# BatteryCharger.net
KiCad netlist of a schematic drawn in Altium Designer
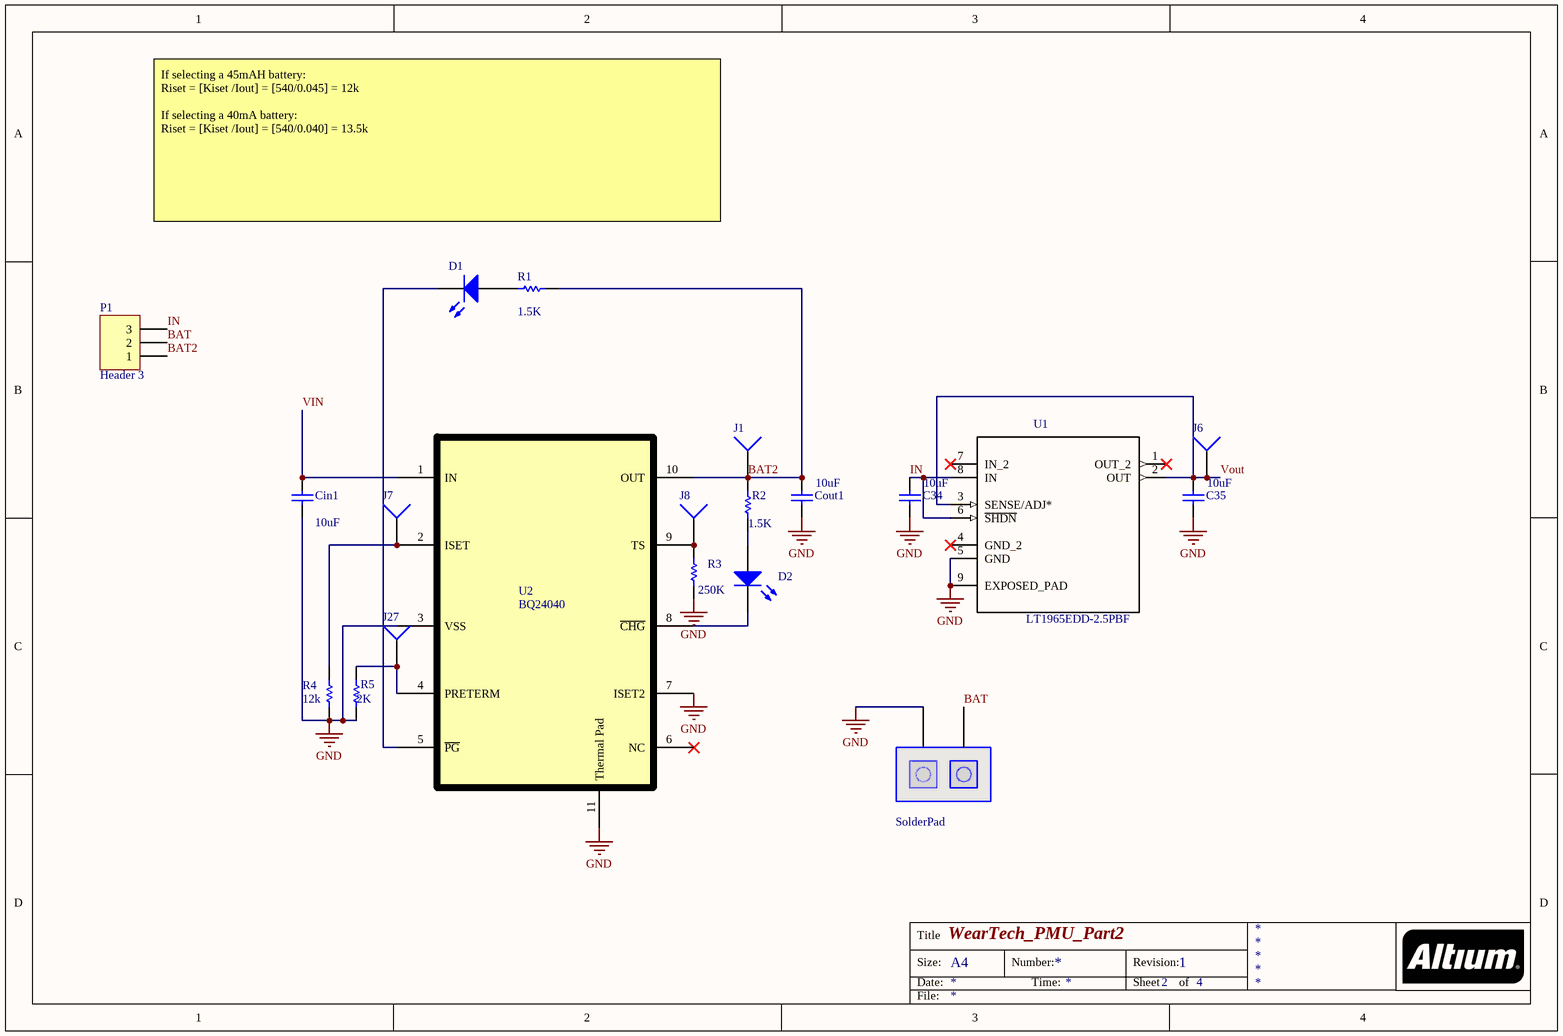
[diagram p0: BatteryCharger.SchDoc]

(export (version "E")
  (design (tool "Eeschema 10.0.6"))
  (components
    (comp (ref "1")
      (value "SolderPad")
      (footprint "bATTERY_CONNECTION")
      (description "Description")
      (fields
        (field (name "MANUFACTURE PART NUM") "Manufacture Part Num")
        (field (name "DIGIKEY PART NUMBER") "D")
      )
      (libsource (lib "WearTechSchLib") (part "SolderPad"))
    )
    (comp (ref "C34")
      (value "10uF")
      (footprint "1608[0603]")
      (description "CAP CER 10UF 4V X5R 0603")
      (fields (field (name "MANUFACTURE PART NUM") "06034D106MAT2A"))
      (libsource (lib "Miscellaneous Devices") (part "Cap"))
    )
    (comp (ref "C35")
      (value "10uF")
      (footprint "1608[0603]")
      (description "CAP CER 10UF 4V X5R 0603")
      (fields (field (name "MANUFACTURE PART NUM") "06034D106MAT2A"))
      (libsource (lib "Miscellaneous Devices") (part "Cap"))
    )
    (comp (ref "Cin1")
      (value "10uF")
      (footprint "1608[0603]")
      (description "CAP CER 10UF 6.3V X5R 0603")
      (fields (field (name "MANUFACTURE PART NUM") "GRM188R60J106ME47D"))
      (libsource (lib "Miscellaneous Devices") (part "Cap"))
    )
    (comp (ref "Cout1")
      (value "10uF")
      (footprint "1608[0603]")
      (description "CAP CER 10UF 4V X5R 0603")
      (fields (field (name "MANUFACTURE PART NUM") "06034D106MAT2A"))
      (libsource (lib "Miscellaneous Devices") (part "Cap"))
    )
    (comp (ref "D1")
      (value "LED0")
      (footprint "1608[0603]")
      (description "LED ORANGE DIFFUSED 0603 SMD")
      (fields (field (name "MANUFACTURE PART NUM") "LO L29K-H2K1-24-Z"))
      (libsource (lib "Miscellaneous Devices") (part "LED0"))
    )
    (comp (ref "D2")
      (value "LED0")
      (footprint "1608[0603]")
      (description "LED ORANGE DIFFUSED 0603 SMD")
      (fields (field (name "MANUFACTURE PART NUM") "LO L29K-H2K1-24-Z"))
      (libsource (lib "Miscellaneous Devices") (part "LED0"))
    )
    (comp (ref "J1")
      (value "Socket")
      (footprint "PIN1")
      (description "Description")
      (fields
        (field (name "MANUFACTURE PART NUM") "68000-200HLF")
        (field (name "DIGIKEY PART NUMBER") "609-5099-1-ND")
      )
      (libsource (lib "Miscellaneous Connectors") (part "Socket"))
    )
    (comp (ref "J6")
      (value "Socket")
      (footprint "PIN1")
      (description "Description")
      (fields
        (field (name "MANUFACTURE PART NUM") "68000-200HLF")
        (field (name "DIGIKEY PART NUMBER") "609-5099-1-ND")
      )
      (libsource (lib "Miscellaneous Connectors") (part "Socket"))
    )
    (comp (ref "J7")
      (value "Socket")
      (footprint "PIN1")
      (description "Description")
      (fields
        (field (name "MANUFACTURE PART NUM") "68000-200HLF")
        (field (name "DIGIKEY PART NUMBER") "609-5099-1-ND")
      )
      (libsource (lib "Miscellaneous Connectors") (part "Socket"))
    )
    (comp (ref "J8")
      (value "Socket")
      (footprint "PIN1")
      (description "Description")
      (fields
        (field (name "MANUFACTURE PART NUM") "68000-200HLF")
        (field (name "DIGIKEY PART NUMBER") "609-5099-1-ND")
      )
      (libsource (lib "Miscellaneous Connectors") (part "Socket"))
    )
    (comp (ref "J27")
      (value "Socket")
      (footprint "PIN1")
      (description "Description")
      (fields
        (field (name "MANUFACTURE PART NUM") "68000-200HLF")
        (field (name "DIGIKEY PART NUMBER") "609-5099-1-ND")
      )
      (libsource (lib "Miscellaneous Connectors") (part "Socket"))
    )
    (comp (ref "P1")
      (value "Header 3")
      (footprint "HDR1X3")
      (description "CONN HEADER 3 POS 2.54")
      (fields (field (name "MANUFACTURE PART NUM") "Manufacture Part Num"))
      (libsource (lib "Miscellaneous Connectors") (part "Header 3"))
    )
    (comp (ref "R1")
      (value "1.5K")
      (footprint "1608[0603]")
      (description "RES SMD 1.5K OHM 5% 1/10W 0603")
      (fields (field (name "MANUFACTURE PART NUM") "RC0603JR-071K5L"))
      (libsource (lib "Miscellaneous Devices") (part "Res1"))
    )
    (comp (ref "R2")
      (value "1.5K")
      (footprint "1608[0603]")
      (description "RES SMD 1.5K OHM 5% 1/10W 0603")
      (fields (field (name "MANUFACTURE PART NUM") "RC0603JR-071K5L"))
      (libsource (lib "Miscellaneous Devices") (part "Res1"))
    )
    (comp (ref "R3")
      (value "250K")
      (footprint "1608[0603]")
      (description "RES SMD 10K OHM 5% 1/16W 0402")
      (fields (field (name "MANUFACTURE PART NUM") "RC0402JR-0710KL"))
      (libsource (lib "Miscellaneous Devices") (part "Res1"))
    )
    (comp (ref "R4")
      (value "12k")
      (footprint "1608[0603]")
      (description "RES SMD 12K OHM 5% 1/10W 0603")
      (fields (field (name "MANUFACTURE PART NUM") "RC0603JR-0712KL"))
      (libsource (lib "Miscellaneous Devices") (part "Res1"))
    )
    (comp (ref "R5")
      (value "2K")
      (footprint "1608[0603]")
      (description "RES SMD 2K OHM 1% 1/10W 0603")
      (fields (field (name "MANUFACTURE PART NUM") "ERJ-3EKF2001V"))
      (libsource (lib "Miscellaneous Devices") (part "Res1"))
    )
    (comp (ref "U1")
      (value "LT1965EDD-2.5PBF")
      (footprint "LT1965")
      (description "IC REG LINEAR 2.5V 1.1A 8DFN")
      (fields (field (name "MANUFACTURE PART NUM") "LT1965IDD-2.5#PBF"))
      (libsource (lib "WearTechSchLib") (part "LT1965EDD-2.5PBF"))
    )
    (comp (ref "U2")
      (value "BQ24040")
      (footprint "BQ24040")
      (description "IC BATT CHG LI-ION 1 CELL 10SON")
      (fields
        (field (name "MANUFACTURE PART NUM") "BQ24040DSQT")
        (field (name "DIGIKEY PART NUMBER") "296-25136-1-ND")
      )
      (libsource (lib "WearTechSchLib") (part "BQ24040"))
    )
  )
  (nets
    (net (code "1") (name "/BAT") (class "Default")
      (node (ref "1") (pin "1") (pinfunction "BAT_1") (pintype "passive"))
      (node (ref "P1") (pin "2") (pinfunction "2_2") (pintype "passive"))
    )
    (net (code "2") (name "/BAT2") (class "Default")
      (node (ref "Cout1") (pin "1") (pinfunction "1_1") (pintype "passive"))
      (node (ref "J1") (pin "1") (pinfunction "1_1") (pintype "passive"))
      (node (ref "P1") (pin "1") (pinfunction "1_1") (pintype "passive"))
      (node (ref "R1") (pin "2") (pinfunction "2_2") (pintype "passive"))
      (node (ref "R2") (pin "1") (pinfunction "1_1") (pintype "passive"))
      (node (ref "U2") (pin "10") (pinfunction "OUT_10") (pintype "passive"))
    )
    (net (code "3") (name "/IN") (class "Default")
      (node (ref "C34") (pin "1") (pinfunction "1_1") (pintype "passive"))
      (node (ref "P1") (pin "3") (pinfunction "3_3") (pintype "passive"))
      (node (ref "U1") (pin "6") (pinfunction "~{SHDN}_6") (pintype "input"))
      (node (ref "U1") (pin "8") (pinfunction "IN_8") (pintype "power_in"))
    )
    (net (code "4") (name "/VIN") (class "Default")
      (node (ref "Cin1") (pin "1") (pinfunction "1_1") (pintype "passive"))
      (node (ref "U2") (pin "1") (pinfunction "IN_1") (pintype "passive"))
    )
    (net (code "5") (name "/Vout") (class "Default")
      (node (ref "C35") (pin "1") (pinfunction "1_1") (pintype "passive"))
      (node (ref "J6") (pin "1") (pinfunction "1_1") (pintype "passive"))
      (node (ref "U1") (pin "2") (pinfunction "OUT_2") (pintype "output"))
      (node (ref "U1") (pin "3") (pinfunction "SENSE/ADJ*_3") (pintype "input"))
    )
    (net (code "6") (name "GND") (class "Default")
      (node (ref "1") (pin "2") (pinfunction "GND_2") (pintype "passive"))
      (node (ref "C34") (pin "2") (pinfunction "2_2") (pintype "passive"))
      (node (ref "C35") (pin "2") (pinfunction "2_2") (pintype "passive"))
      (node (ref "Cin1") (pin "2") (pinfunction "2_2") (pintype "passive"))
      (node (ref "Cout1") (pin "2") (pinfunction "2_2") (pintype "passive"))
      (node (ref "R3") (pin "1") (pinfunction "1_1") (pintype "passive"))
      (node (ref "R4") (pin "2") (pinfunction "2_2") (pintype "passive"))
      (node (ref "R5") (pin "2") (pinfunction "2_2") (pintype "passive"))
      (node (ref "U1") (pin "5") (pinfunction "GND_5") (pintype "passive"))
      (node (ref "U1") (pin "9") (pinfunction "EXPOSED_PAD_9") (pintype "passive"))
      (node (ref "U2") (pin "11") (pinfunction "Thermal_Pad_11") (pintype "passive"))
      (node (ref "U2") (pin "3") (pinfunction "VSS_3") (pintype "passive"))
      (node (ref "U2") (pin "7") (pinfunction "ISET2_7") (pintype "passive"))
    )
    (net (code "7") (name "Net-(D1-A)") (class "Default")
      (node (ref "D1") (pin "1") (pinfunction "A_1") (pintype "passive"))
      (node (ref "R1") (pin "1") (pinfunction "1_1") (pintype "passive"))
    )
    (net (code "8") (name "Net-(D1-K)") (class "Default")
      (node (ref "D1") (pin "2") (pinfunction "K_2") (pintype "passive"))
      (node (ref "U2") (pin "5") (pinfunction "~{PG}_5") (pintype "passive"))
    )
    (net (code "9") (name "Net-(D2-A)") (class "Default")
      (node (ref "D2") (pin "1") (pinfunction "A_1") (pintype "passive"))
      (node (ref "R2") (pin "2") (pinfunction "2_2") (pintype "passive"))
    )
    (net (code "10") (name "Net-(D2-K)") (class "Default")
      (node (ref "D2") (pin "2") (pinfunction "K_2") (pintype "passive"))
      (node (ref "U2") (pin "8") (pinfunction "~{CHG}_8") (pintype "passive"))
    )
    (net (code "11") (name "Net-(U2-ISET)") (class "Default")
      (node (ref "J7") (pin "1") (pinfunction "1_1") (pintype "passive"))
      (node (ref "R4") (pin "1") (pinfunction "1_1") (pintype "passive"))
      (node (ref "U2") (pin "2") (pinfunction "ISET_2") (pintype "passive"))
    )
    (net (code "12") (name "Net-(U2-PRETERM)") (class "Default")
      (node (ref "J27") (pin "1") (pinfunction "1_1") (pintype "passive"))
      (node (ref "R5") (pin "1") (pinfunction "1_1") (pintype "passive"))
      (node (ref "U2") (pin "4") (pinfunction "PRETERM_4") (pintype "passive"))
    )
    (net (code "13") (name "Net-(U2-TS)") (class "Default")
      (node (ref "J8") (pin "1") (pinfunction "1_1") (pintype "passive"))
      (node (ref "R3") (pin "2") (pinfunction "2_2") (pintype "passive"))
      (node (ref "U2") (pin "9") (pinfunction "TS_9") (pintype "passive"))
    )
    (net (code "14") (name "unconnected-(U1-GND_2-Pad4)") (class "Default")
      (node (ref "U1") (pin "4") (pinfunction "GND_2_4") (pintype "passive+no_connect"))
    )
    (net (code "15") (name "unconnected-(U1-IN_2-Pad7)") (class "Default")
      (node (ref "U1") (pin "7") (pinfunction "IN_2_7") (pintype "power_in+no_connect"))
    )
    (net (code "16") (name "unconnected-(U1-OUT_2-Pad1)") (class "Default")
      (node (ref "U1") (pin "1") (pinfunction "OUT_2_1") (pintype "output+no_connect"))
    )
    (net (code "17") (name "unconnected-(U2-NC-Pad6)") (class "Default")
      (node (ref "U2") (pin "6") (pinfunction "NC_6") (pintype "passive+no_connect"))
    )
  )
)
